# smartproj_ready.net
KiCad netlist of a schematic drawn in EAGLE
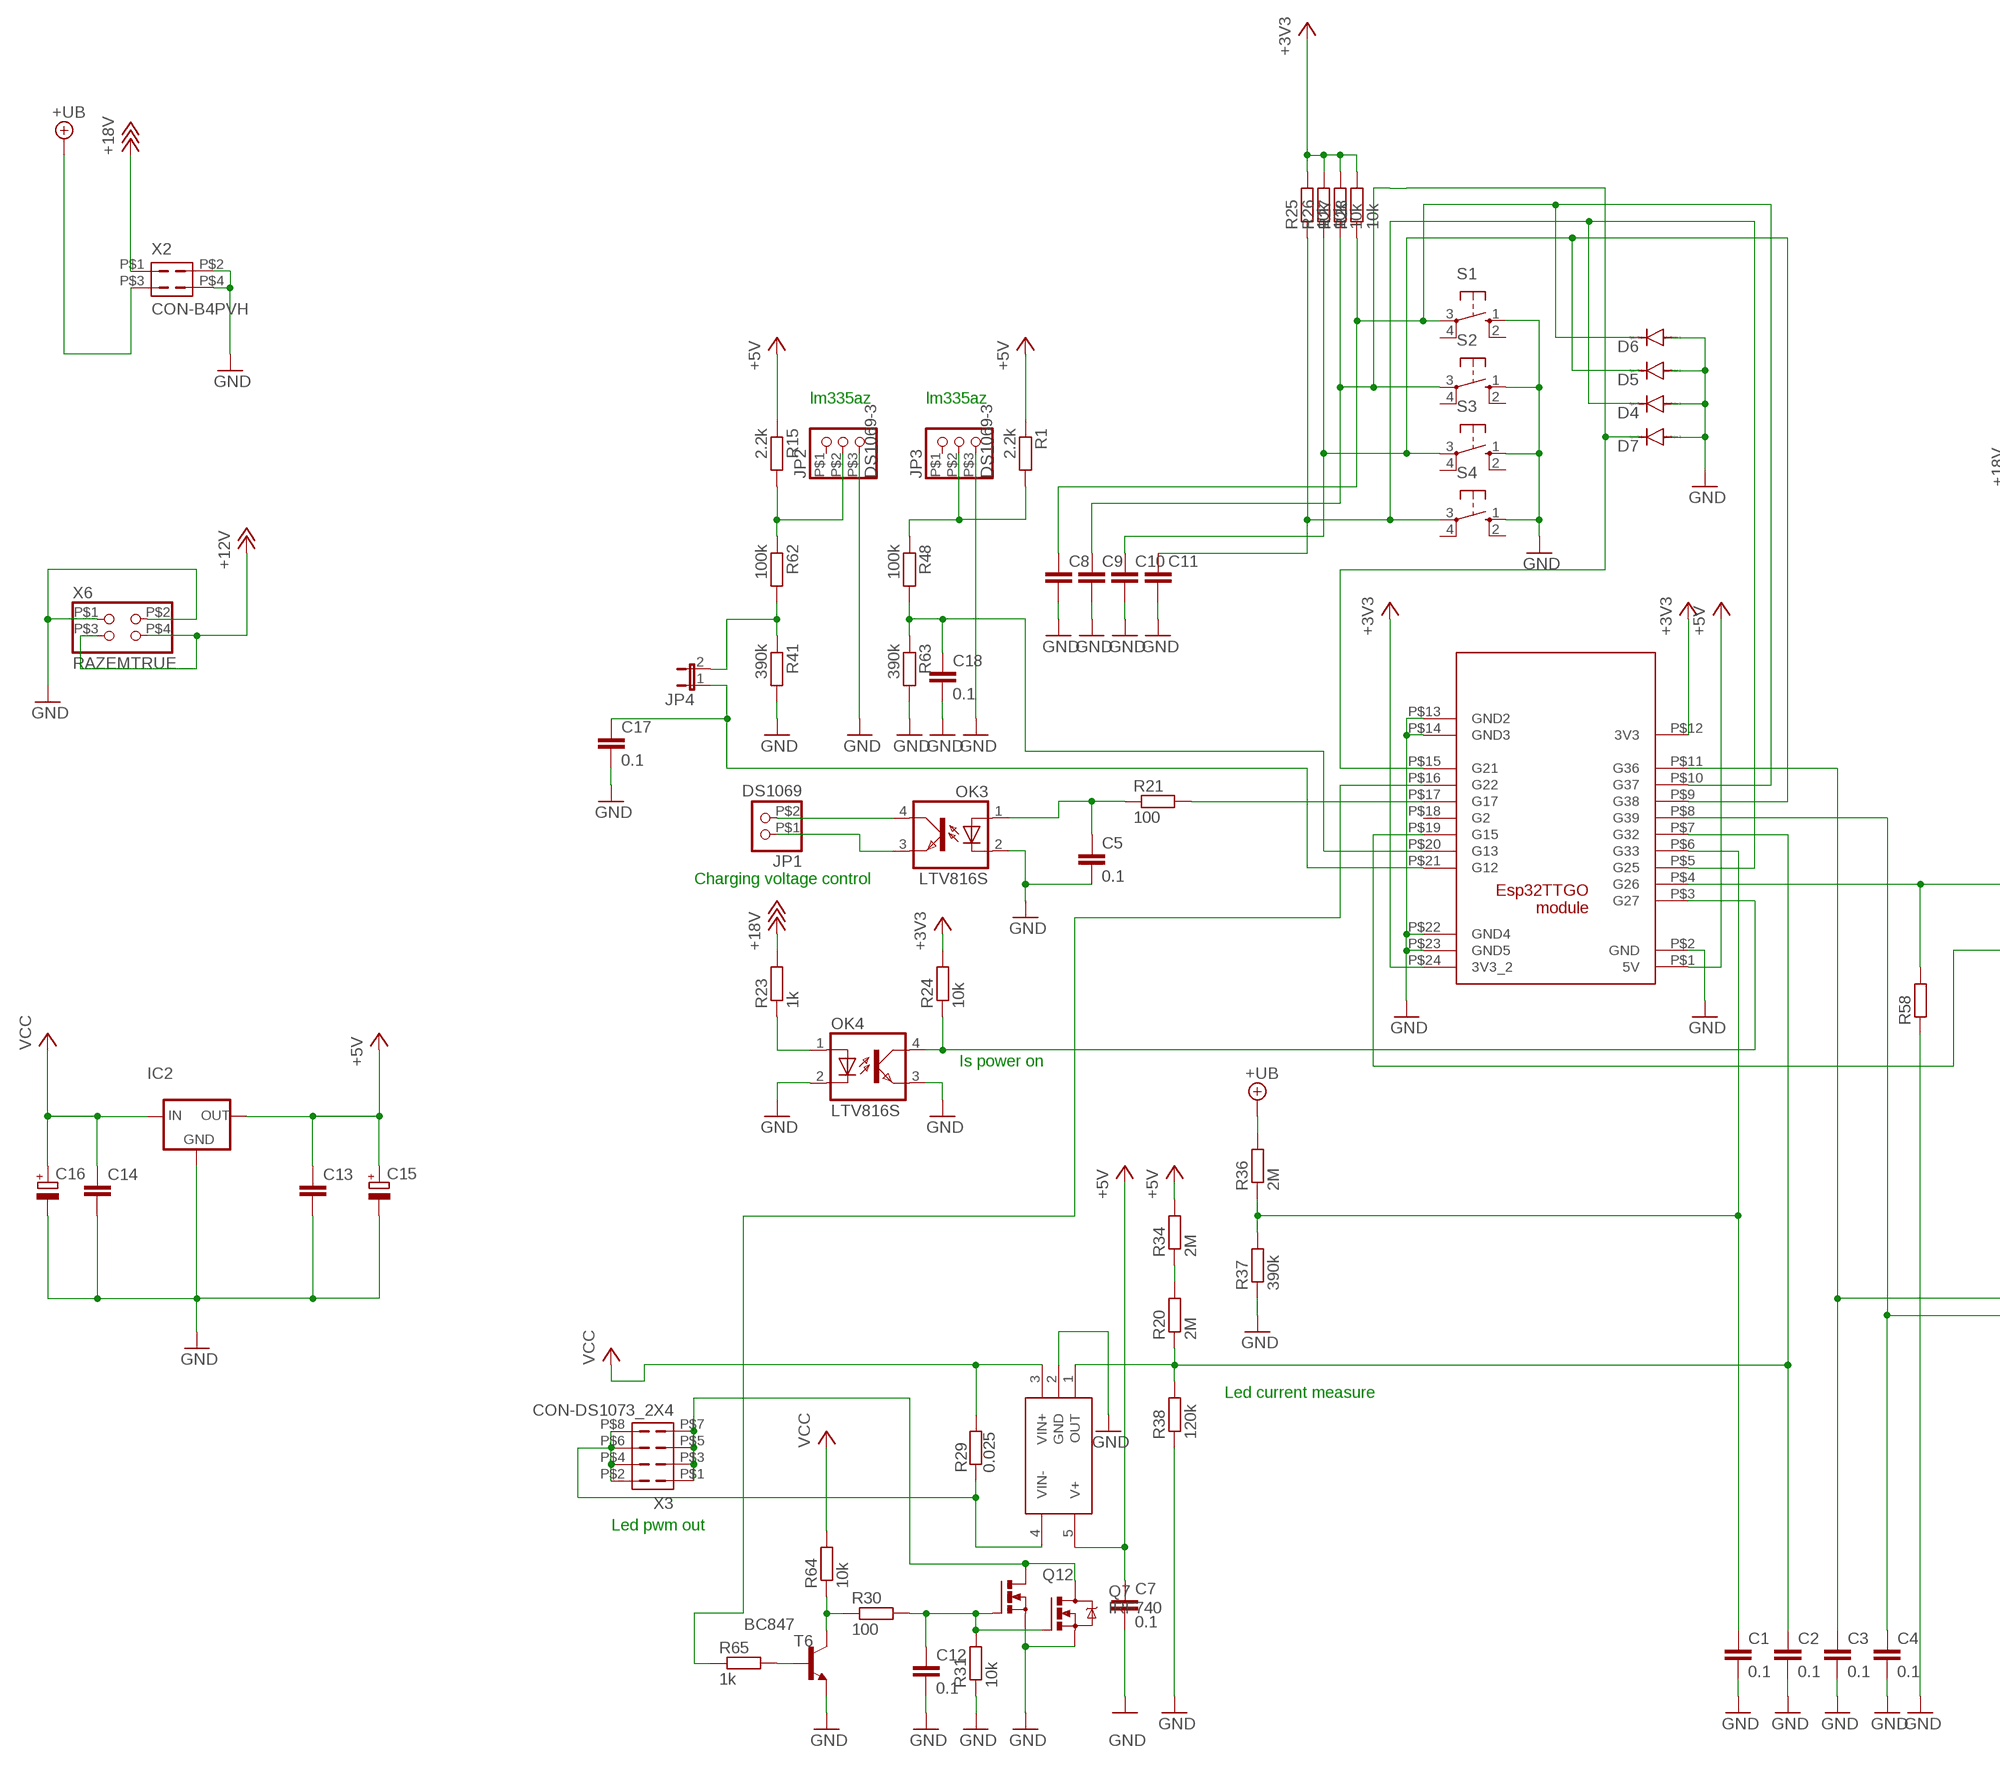
[diagram p0: schematic, sheet 1, part 1 of 2]
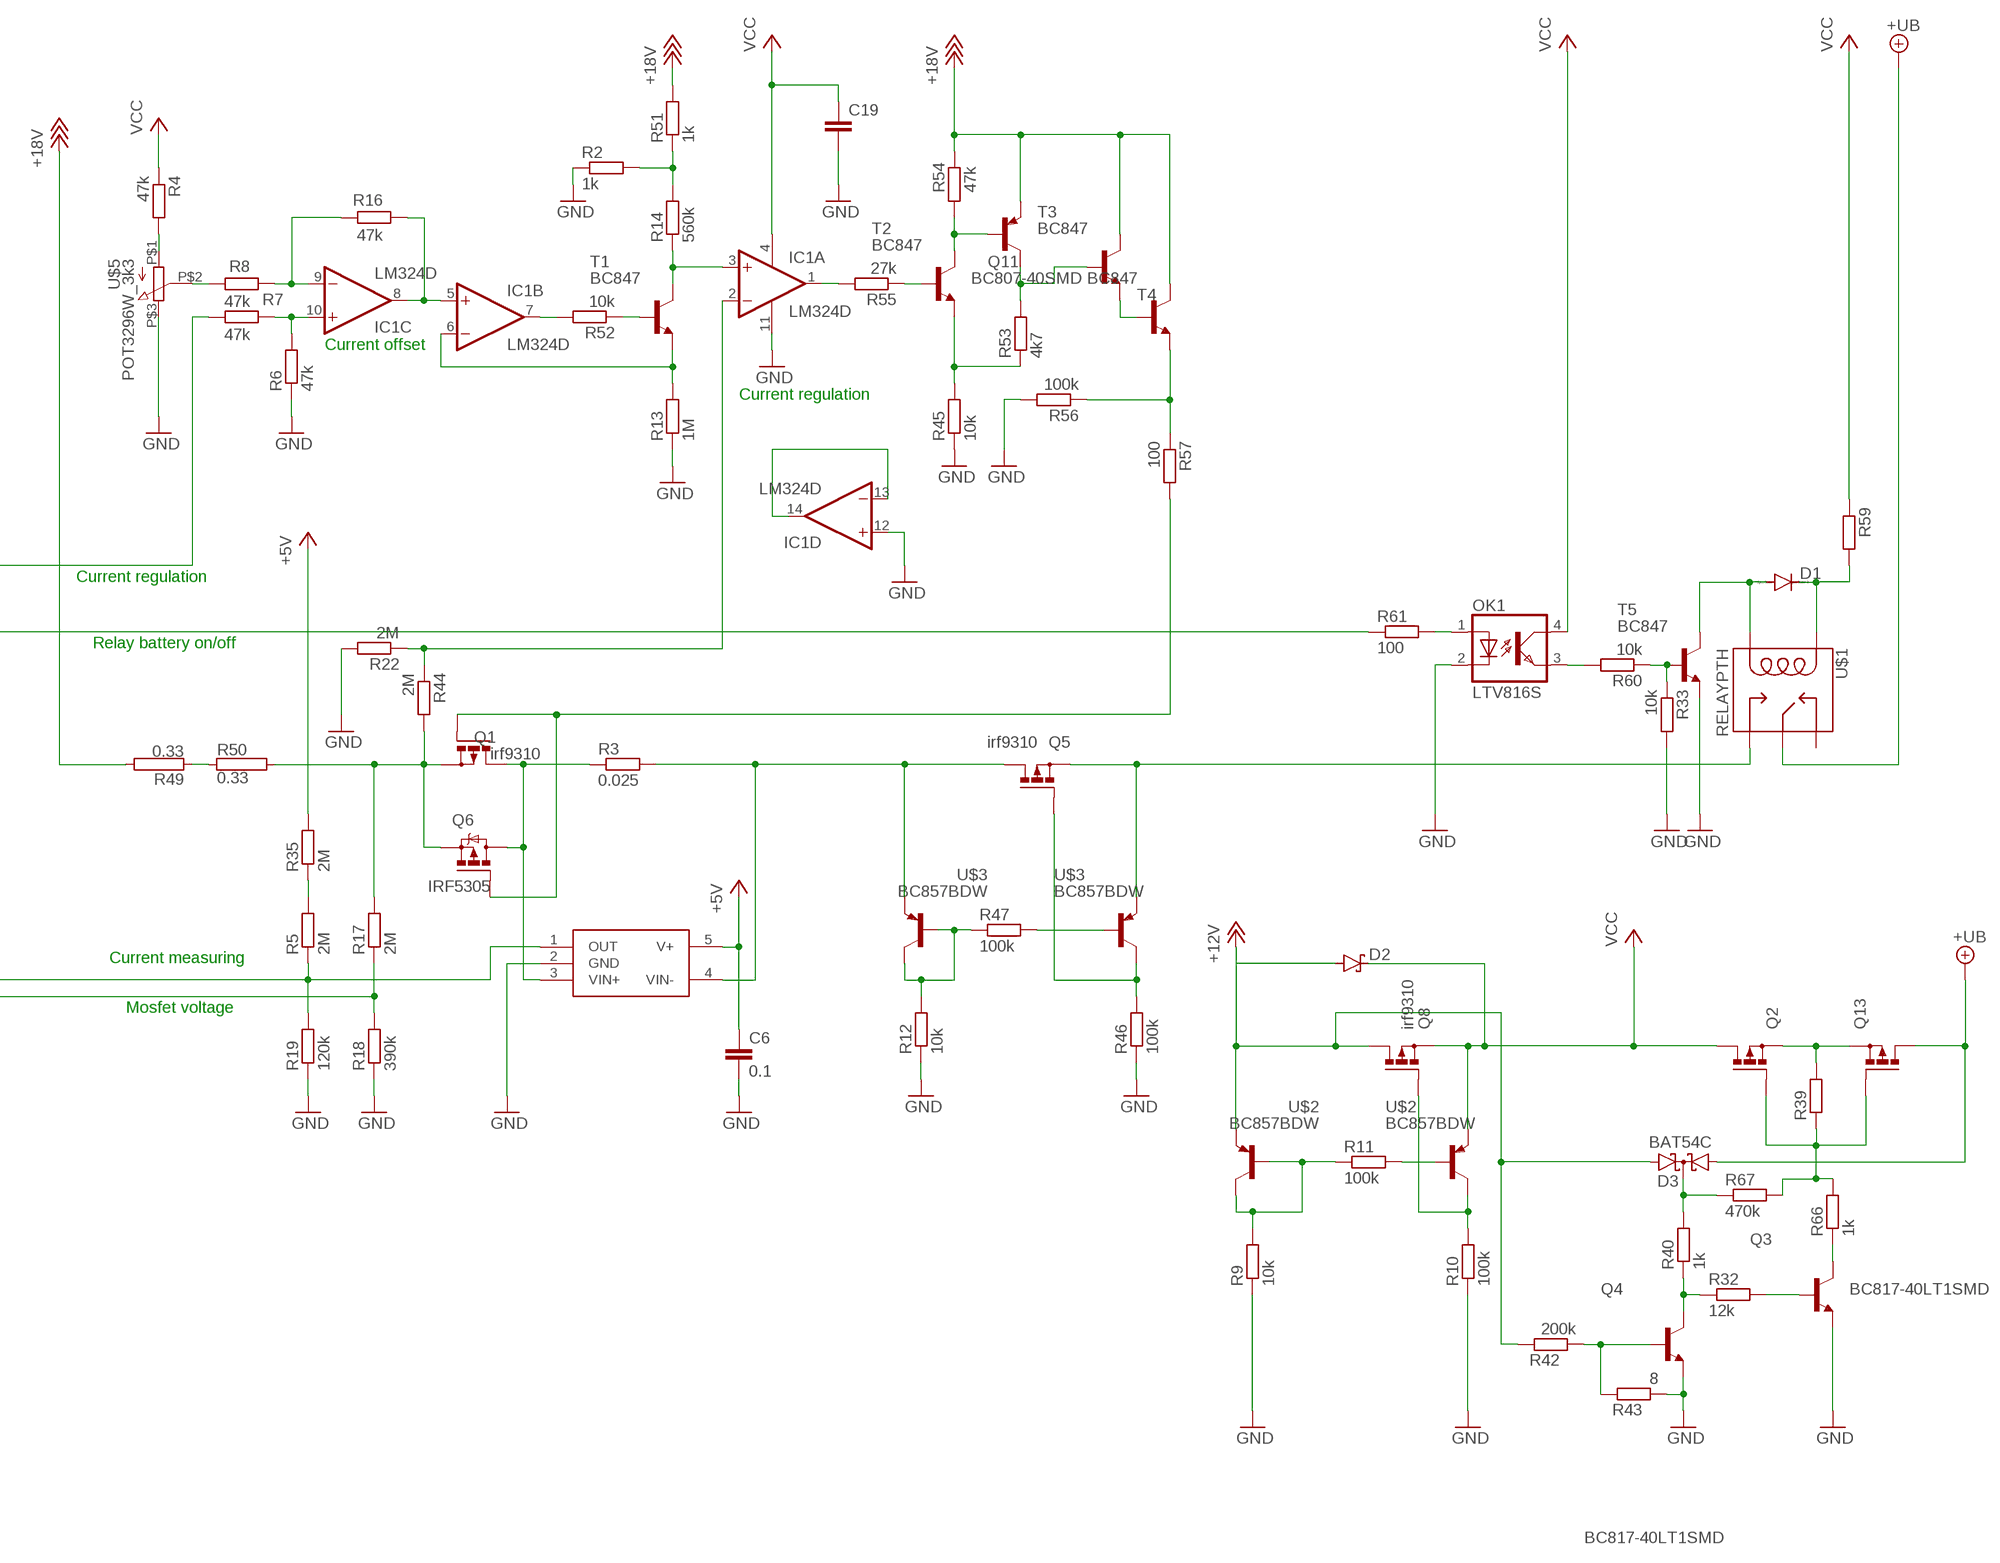
[diagram p1: schematic, sheet 1, part 2 of 2]

(export (version "E")
  (design (tool "Eeschema 10.0.6"))
  (components
    (comp (ref "C1")
      (value "0.1")
      (footprint "eagle-import:C0603K")
      (libsource (lib "eagle-import") (part "C-EUC0603K"))
    )
    (comp (ref "C2")
      (value "0.1")
      (footprint "eagle-import:C0603K")
      (libsource (lib "eagle-import") (part "C-EUC0603K"))
    )
    (comp (ref "C3")
      (value "0.1")
      (footprint "eagle-import:C0603K")
      (libsource (lib "eagle-import") (part "C-EUC0603K"))
    )
    (comp (ref "C4")
      (value "0.1")
      (footprint "eagle-import:C0603K")
      (libsource (lib "eagle-import") (part "C-EUC0603K"))
    )
    (comp (ref "C5")
      (value "0.1")
      (footprint "eagle-import:C0603K")
      (libsource (lib "eagle-import") (part "C-EUC0603K"))
    )
    (comp (ref "C6")
      (value "0.1")
      (footprint "eagle-import:C0603K")
      (libsource (lib "eagle-import") (part "C-EUC0603K"))
    )
    (comp (ref "C7")
      (value "0.1")
      (footprint "eagle-import:C0603K")
      (libsource (lib "eagle-import") (part "C-EUC0603K"))
    )
    (comp (ref "C8")
      (value "C-EUC0603K")
      (footprint "eagle-import:C0603K")
      (libsource (lib "eagle-import") (part "C-EUC0603K"))
    )
    (comp (ref "C9")
      (value "C-EUC0603K")
      (footprint "eagle-import:C0603K")
      (libsource (lib "eagle-import") (part "C-EUC0603K"))
    )
    (comp (ref "C10")
      (value "C-EUC0603K")
      (footprint "eagle-import:C0603K")
      (libsource (lib "eagle-import") (part "C-EUC0603K"))
    )
    (comp (ref "C11")
      (value "C-EUC0603K")
      (footprint "eagle-import:C0603K")
      (libsource (lib "eagle-import") (part "C-EUC0603K"))
    )
    (comp (ref "C12")
      (value "0.1")
      (footprint "eagle-import:C0603K")
      (libsource (lib "eagle-import") (part "C-EUC0603K"))
    )
    (comp (ref "C13")
      (value "C-EUC0603")
      (footprint "eagle-import:C0603")
      (libsource (lib "eagle-import") (part "C-EUC0603"))
    )
    (comp (ref "C14")
      (value "C-EUC0603")
      (footprint "eagle-import:C0603")
      (libsource (lib "eagle-import") (part "C-EUC0603"))
    )
    (comp (ref "C15")
      (value "CPOL-EUSMCE")
      (footprint "eagle-import:SMC_E")
      (libsource (lib "eagle-import") (part "CPOL-EUSMCE"))
    )
    (comp (ref "C16")
      (value "CPOL-EUSMCE")
      (footprint "eagle-import:SMC_E")
      (libsource (lib "eagle-import") (part "CPOL-EUSMCE"))
    )
    (comp (ref "C17")
      (value "0.1")
      (footprint "eagle-import:C0603K")
      (libsource (lib "eagle-import") (part "C-EUC0603K"))
    )
    (comp (ref "C18")
      (value "0.1")
      (footprint "eagle-import:C0603K")
      (libsource (lib "eagle-import") (part "C-EUC0603K"))
    )
    (comp (ref "C19")
      (value "C-EUC0603K")
      (footprint "eagle-import:C0603K")
      (libsource (lib "eagle-import") (part "C-EUC0603K"))
    )
    (comp (ref "D1")
      (value "DIODE-DO214AC")
      (footprint "eagle-import:DO214AC")
      (libsource (lib "eagle-import") (part "DIODE-DO214AC"))
    )
    (comp (ref "D2")
      (value "SCHOTTKY-DIODESMC")
      (footprint "eagle-import:SMC")
      (libsource (lib "eagle-import") (part "SCHOTTKY-DIODESMC"))
    )
    (comp (ref "D3")
      (value "BAT54C")
      (footprint "eagle-import:SOT23")
      (libsource (lib "eagle-import") (part "BAT54C"))
    )
    (comp (ref "D4")
      (value "DIODE-SOD323-W")
      (footprint "eagle-import:SOD323-W")
      (libsource (lib "eagle-import") (part "DIODE-SOD323-W"))
    )
    (comp (ref "D5")
      (value "DIODE-SOD323-W")
      (footprint "eagle-import:SOD323-W")
      (libsource (lib "eagle-import") (part "DIODE-SOD323-W"))
    )
    (comp (ref "D6")
      (value "DIODE-SOD323-W")
      (footprint "eagle-import:SOD323-W")
      (libsource (lib "eagle-import") (part "DIODE-SOD323-W"))
    )
    (comp (ref "D7")
      (value "DIODE-SOD323-W")
      (footprint "eagle-import:SOD323-W")
      (libsource (lib "eagle-import") (part "DIODE-SOD323-W"))
    )
    (comp (ref "IC1")
      (value "LM324D")
      (footprint "eagle-import:SO14")
      (libsource (lib "eagle-import") (part "LM324D"))
    )
    (comp (ref "IC2")
      (value "78XXS")
      (footprint "eagle-import:78XXS")
      (libsource (lib "eagle-import") (part "78XXS"))
    )
    (comp (ref "JP1")
      (value "DS1069")
      (footprint "eagle-import:DS1069-2")
      (libsource (lib "eagle-import") (part "DS1069"))
    )
    (comp (ref "JP2")
      (value "DS1069-3")
      (footprint "eagle-import:DS1069-3")
      (libsource (lib "eagle-import") (part "DS1069-3"))
    )
    (comp (ref "JP3")
      (value "DS1069-3")
      (footprint "eagle-import:DS1069-3")
      (libsource (lib "eagle-import") (part "DS1069-3"))
    )
    (comp (ref "JP4")
      (value "JP1E")
      (footprint "eagle-import:JP1")
      (libsource (lib "eagle-import") (part "JP1E"))
    )
    (comp (ref "OK1")
      (value "LTV816S")
      (footprint "eagle-import:DIL4-SMD")
      (libsource (lib "eagle-import") (part "LTV816S"))
    )
    (comp (ref "OK3")
      (value "LTV816S")
      (footprint "eagle-import:DIL4-SMD")
      (libsource (lib "eagle-import") (part "LTV816S"))
    )
    (comp (ref "OK4")
      (value "LTV816S")
      (footprint "eagle-import:DIL4-SMD")
      (libsource (lib "eagle-import") (part "LTV816S"))
    )
    (comp (ref "Q1")
      (value "irf9310")
      (footprint "eagle-import:SO-08")
      (libsource (lib "eagle-import") (part "P-MOSFET-SO8"))
    )
    (comp (ref "Q2")
      (value "P-MOSFET-SO8")
      (footprint "eagle-import:SO-08")
      (libsource (lib "eagle-import") (part "P-MOSFET-SO8"))
    )
    (comp (ref "Q3")
      (value "BC817-40LT1SMD")
      (footprint "eagle-import:SOT23-BEC")
      (libsource (lib "eagle-import") (part "BC817SMD-40LT1"))
    )
    (comp (ref "Q4")
      (value "BC817-40LT1SMD")
      (footprint "eagle-import:SOT23-BEC")
      (libsource (lib "eagle-import") (part "BC817SMD-40LT1"))
    )
    (comp (ref "Q5")
      (value "irf9310")
      (footprint "eagle-import:SO-08")
      (libsource (lib "eagle-import") (part "P-MOSFET-SO8"))
    )
    (comp (ref "Q6")
      (value "IRF5305")
      (footprint "eagle-import:TO220BV")
      (libsource (lib "eagle-import") (part "IRF9530"))
    )
    (comp (ref "Q7")
      (value "IRF740")
      (footprint "eagle-import:TO220BV")
      (libsource (lib "eagle-import") (part "IRF740"))
    )
    (comp (ref "Q8")
      (value "irf9310")
      (footprint "eagle-import:SO-08")
      (libsource (lib "eagle-import") (part "P-MOSFET-SO8"))
    )
    (comp (ref "Q11")
      (value "BC807-40SMD")
      (footprint "eagle-import:SOT23-BEC")
      (libsource (lib "eagle-import") (part "BC807SMD-40"))
    )
    (comp (ref "Q12")
      (value "N-MOSFET-SO8S")
      (footprint "eagle-import:SO-08")
      (libsource (lib "eagle-import") (part "N-MOSFET-SO8S"))
    )
    (comp (ref "Q13")
      (value "P-MOSFET-SO8")
      (footprint "eagle-import:SO-08")
      (libsource (lib "eagle-import") (part "P-MOSFET-SO8"))
    )
    (comp (ref "R1")
      (value "2.2k")
      (footprint "eagle-import:R0603")
      (libsource (lib "eagle-import") (part "resistor_348_R-EU_R0603"))
    )
    (comp (ref "R2")
      (value "1k")
      (footprint "eagle-import:R0603")
      (libsource (lib "eagle-import") (part "R-EU_R0603"))
    )
    (comp (ref "R3")
      (value "0.025")
      (footprint "eagle-import:R2512")
      (libsource (lib "eagle-import") (part "R-EU_R2512"))
    )
    (comp (ref "R4")
      (value "47k")
      (footprint "eagle-import:R0603")
      (libsource (lib "eagle-import") (part "resistor_348_R-EU_R0603"))
    )
    (comp (ref "R5")
      (value "2M")
      (footprint "eagle-import:R0603")
      (libsource (lib "eagle-import") (part "resistor_348_R-EU_R0603"))
    )
    (comp (ref "R6")
      (value "47k")
      (footprint "eagle-import:R0603")
      (libsource (lib "eagle-import") (part "resistor_348_R-EU_R0603"))
    )
    (comp (ref "R7")
      (value "47k")
      (footprint "eagle-import:R0603")
      (libsource (lib "eagle-import") (part "resistor_348_R-EU_R0603"))
    )
    (comp (ref "R8")
      (value "47k")
      (footprint "eagle-import:R0603")
      (libsource (lib "eagle-import") (part "resistor_348_R-EU_R0603"))
    )
    (comp (ref "R9")
      (value "10k")
      (footprint "eagle-import:R0603")
      (libsource (lib "eagle-import") (part "R-EU_R0603"))
    )
    (comp (ref "R10")
      (value "100k")
      (footprint "eagle-import:R0603")
      (libsource (lib "eagle-import") (part "R-EU_R0603"))
    )
    (comp (ref "R11")
      (value "100k")
      (footprint "eagle-import:R0603")
      (libsource (lib "eagle-import") (part "R-EU_R0603"))
    )
    (comp (ref "R12")
      (value "10k")
      (footprint "eagle-import:R0603")
      (libsource (lib "eagle-import") (part "R-EU_R0603"))
    )
    (comp (ref "R13")
      (value "1M")
      (footprint "eagle-import:R0603")
      (libsource (lib "eagle-import") (part "R-EU_R0603"))
    )
    (comp (ref "R14")
      (value "560k")
      (footprint "eagle-import:R0603")
      (libsource (lib "eagle-import") (part "R-EU_R0603"))
    )
    (comp (ref "R15")
      (value "2.2k")
      (footprint "eagle-import:R0603")
      (libsource (lib "eagle-import") (part "resistor_348_R-EU_R0603"))
    )
    (comp (ref "R16")
      (value "47k")
      (footprint "eagle-import:R0603")
      (libsource (lib "eagle-import") (part "resistor_348_R-EU_R0603"))
    )
    (comp (ref "R17")
      (value "2M")
      (footprint "eagle-import:R0603")
      (libsource (lib "eagle-import") (part "resistor_348_R-EU_R0603"))
    )
    (comp (ref "R18")
      (value "390k")
      (footprint "eagle-import:R0603")
      (libsource (lib "eagle-import") (part "resistor_348_R-EU_R0603"))
    )
    (comp (ref "R19")
      (value "120k")
      (footprint "eagle-import:R0603")
      (libsource (lib "eagle-import") (part "resistor_348_R-EU_R0603"))
    )
    (comp (ref "R20")
      (value "2M")
      (footprint "eagle-import:R0603")
      (libsource (lib "eagle-import") (part "resistor_348_R-EU_R0603"))
    )
    (comp (ref "R21")
      (value "100")
      (footprint "eagle-import:R0603")
      (libsource (lib "eagle-import") (part "resistor_348_R-EU_R0603"))
    )
    (comp (ref "R22")
      (value "2M")
      (footprint "eagle-import:R0603")
      (libsource (lib "eagle-import") (part "resistor_348_R-EU_R0603"))
    )
    (comp (ref "R23")
      (value "1k")
      (footprint "eagle-import:R0603")
      (libsource (lib "eagle-import") (part "R-EU_R0603"))
    )
    (comp (ref "R24")
      (value "10k")
      (footprint "eagle-import:R0603")
      (libsource (lib "eagle-import") (part "R-EU_R0603"))
    )
    (comp (ref "R25")
      (value "10k")
      (footprint "eagle-import:R0603")
      (libsource (lib "eagle-import") (part "R-EU_R0603"))
    )
    (comp (ref "R26")
      (value "10k")
      (footprint "eagle-import:R0603")
      (libsource (lib "eagle-import") (part "R-EU_R0603"))
    )
    (comp (ref "R27")
      (value "10k")
      (footprint "eagle-import:R0603")
      (libsource (lib "eagle-import") (part "R-EU_R0603"))
    )
    (comp (ref "R28")
      (value "10k")
      (footprint "eagle-import:R0603")
      (libsource (lib "eagle-import") (part "R-EU_R0603"))
    )
    (comp (ref "R29")
      (value "0.025")
      (footprint "eagle-import:R2512")
      (libsource (lib "eagle-import") (part "R-EU_R2512"))
    )
    (comp (ref "R30")
      (value "100")
      (footprint "eagle-import:R0603")
      (libsource (lib "eagle-import") (part "resistor_348_R-EU_R0603"))
    )
    (comp (ref "R31")
      (value "10k")
      (footprint "eagle-import:R0603")
      (libsource (lib "eagle-import") (part "resistor_348_R-EU_R0603"))
    )
    (comp (ref "R32")
      (value "12k")
      (footprint "eagle-import:R0603")
      (libsource (lib "eagle-import") (part "R-EU_R0603"))
    )
    (comp (ref "R33")
      (value "10k")
      (footprint "eagle-import:R0603")
      (libsource (lib "eagle-import") (part "R-EU_R0603"))
    )
    (comp (ref "R34")
      (value "2M")
      (footprint "eagle-import:R0603")
      (libsource (lib "eagle-import") (part "resistor_348_R-EU_R0603"))
    )
    (comp (ref "R35")
      (value "2M")
      (footprint "eagle-import:R0603")
      (libsource (lib "eagle-import") (part "resistor_348_R-EU_R0603"))
    )
    (comp (ref "R36")
      (value "2M")
      (footprint "eagle-import:R0603")
      (libsource (lib "eagle-import") (part "R-EU_R0603"))
    )
    (comp (ref "R37")
      (value "390k")
      (footprint "eagle-import:R0603")
      (libsource (lib "eagle-import") (part "R-EU_R0603"))
    )
    (comp (ref "R38")
      (value "120k")
      (footprint "eagle-import:R0603")
      (libsource (lib "eagle-import") (part "resistor_348_R-EU_R0603"))
    )
    (comp (ref "R39")
      (value "R-EU_R0603")
      (footprint "eagle-import:R0603")
      (libsource (lib "eagle-import") (part "R-EU_R0603"))
    )
    (comp (ref "R40")
      (value "1k")
      (footprint "eagle-import:R0603")
      (libsource (lib "eagle-import") (part "R-EU_R0603"))
    )
    (comp (ref "R41")
      (value "390k")
      (footprint "eagle-import:R0603")
      (libsource (lib "eagle-import") (part "resistor_348_R-EU_R0603"))
    )
    (comp (ref "R42")
      (value "200k")
      (footprint "eagle-import:R0603")
      (libsource (lib "eagle-import") (part "R-EU_R0603"))
    )
    (comp (ref "R43")
      (value "8")
      (footprint "eagle-import:R0603")
      (libsource (lib "eagle-import") (part "R-EU_R0603"))
    )
    (comp (ref "R44")
      (value "2M")
      (footprint "eagle-import:R0603")
      (libsource (lib "eagle-import") (part "resistor_348_R-EU_R0603"))
    )
    (comp (ref "R45")
      (value "10k")
      (footprint "eagle-import:R0603")
      (libsource (lib "eagle-import") (part "R-EU_R0603"))
    )
    (comp (ref "R46")
      (value "100k")
      (footprint "eagle-import:R0603")
      (libsource (lib "eagle-import") (part "R-EU_R0603"))
    )
    (comp (ref "R47")
      (value "100k")
      (footprint "eagle-import:R0603")
      (libsource (lib "eagle-import") (part "R-EU_R0603"))
    )
    (comp (ref "R48")
      (value "100k")
      (footprint "eagle-import:R0603")
      (libsource (lib "eagle-import") (part "resistor_348_R-EU_R0603"))
    )
    (comp (ref "R49")
      (value "0.33")
      (footprint "eagle-import:CA4220")
      (libsource (lib "eagle-import") (part "RCA4220"))
    )
    (comp (ref "R50")
      (value "0.33")
      (footprint "eagle-import:CA4220")
      (libsource (lib "eagle-import") (part "RCA4220"))
    )
    (comp (ref "R51")
      (value "1k")
      (footprint "eagle-import:R0603")
      (libsource (lib "eagle-import") (part "R-EU_R0603"))
    )
    (comp (ref "R52")
      (value "10k")
      (footprint "eagle-import:R0603")
      (libsource (lib "eagle-import") (part "R-EU_R0603"))
    )
    (comp (ref "R53")
      (value "4k7")
      (footprint "eagle-import:R0603")
      (libsource (lib "eagle-import") (part "R-EU_R0603"))
    )
    (comp (ref "R54")
      (value "47k")
      (footprint "eagle-import:R0603")
      (libsource (lib "eagle-import") (part "R-EU_R0603"))
    )
    (comp (ref "R55")
      (value "27k")
      (footprint "eagle-import:R0603")
      (libsource (lib "eagle-import") (part "R-EU_R0603"))
    )
    (comp (ref "R56")
      (value "100k")
      (footprint "eagle-import:R0603")
      (libsource (lib "eagle-import") (part "R-EU_R0603"))
    )
    (comp (ref "R57")
      (value "100")
      (footprint "eagle-import:R0603")
      (libsource (lib "eagle-import") (part "R-EU_R0603"))
    )
    (comp (ref "R58")
      (value "R-EU_R0603")
      (footprint "eagle-import:R0603")
      (libsource (lib "eagle-import") (part "R-EU_R0603"))
    )
    (comp (ref "R59")
      (value "R-EU_R1206")
      (footprint "eagle-import:R1206")
      (libsource (lib "eagle-import") (part "R-EU_R1206"))
    )
    (comp (ref "R60")
      (value "10k")
      (footprint "eagle-import:R0603")
      (libsource (lib "eagle-import") (part "R-EU_R0603"))
    )
    (comp (ref "R61")
      (value "100")
      (footprint "eagle-import:R0603")
      (libsource (lib "eagle-import") (part "R-EU_R0603"))
    )
    (comp (ref "R62")
      (value "100k")
      (footprint "eagle-import:R0603")
      (libsource (lib "eagle-import") (part "resistor_348_R-EU_R0603"))
    )
    (comp (ref "R63")
      (value "390k")
      (footprint "eagle-import:R0603")
      (libsource (lib "eagle-import") (part "resistor_348_R-EU_R0603"))
    )
    (comp (ref "R64")
      (value "10k")
      (footprint "eagle-import:R0603")
      (libsource (lib "eagle-import") (part "resistor_348_R-EU_R0603"))
    )
    (comp (ref "R65")
      (value "1k")
      (footprint "eagle-import:R0603")
      (libsource (lib "eagle-import") (part "resistor_348_R-EU_R0603"))
    )
    (comp (ref "R66")
      (value "1k")
      (footprint "eagle-import:R0603")
      (libsource (lib "eagle-import") (part "R-EU_R0603"))
    )
    (comp (ref "R67")
      (value "470k")
      (footprint "eagle-import:R0603")
      (libsource (lib "eagle-import") (part "R-EU_R0603"))
    )
    (comp (ref "S1")
      (value "10-XX")
      (footprint "eagle-import:B3F-10XX")
      (fields (field (name "MPN") "B3F-1000"))
      (libsource (lib "eagle-import") (part "10-XX"))
    )
    (comp (ref "S2")
      (value "10-XX")
      (footprint "eagle-import:B3F-10XX")
      (fields (field (name "MPN") "B3F-1000"))
      (libsource (lib "eagle-import") (part "10-XX"))
    )
    (comp (ref "S3")
      (value "10-XX")
      (footprint "eagle-import:B3F-10XX")
      (fields (field (name "MPN") "B3F-1000"))
      (libsource (lib "eagle-import") (part "10-XX"))
    )
    (comp (ref "S4")
      (value "10-XX")
      (footprint "eagle-import:B3F-10XX")
      (fields (field (name "MPN") "B3F-1000"))
      (libsource (lib "eagle-import") (part "10-XX"))
    )
    (comp (ref "T1")
      (value "BC847")
      (footprint "eagle-import:SOT23")
      (libsource (lib "eagle-import") (part "BC847"))
    )
    (comp (ref "T2")
      (value "BC847")
      (footprint "eagle-import:SOT23")
      (libsource (lib "eagle-import") (part "BC847"))
    )
    (comp (ref "T3")
      (value "BC847")
      (footprint "eagle-import:SOT23")
      (libsource (lib "eagle-import") (part "BC847"))
    )
    (comp (ref "T4")
      (value "BC847")
      (footprint "eagle-import:SOT23")
      (libsource (lib "eagle-import") (part "BC847"))
    )
    (comp (ref "T5")
      (value "BC847")
      (footprint "eagle-import:SOT23")
      (libsource (lib "eagle-import") (part "BC847"))
    )
    (comp (ref "T6")
      (value "BC847")
      (footprint "eagle-import:SOT23")
      (libsource (lib "eagle-import") (part "BC847"))
    )
    (comp (ref "U$1")
      (value "RELAYPTH")
      (footprint "eagle-import:SRD-05VDC-SL-C")
      (libsource (lib "eagle-import") (part "RELAYPTH"))
    )
    (comp (ref "U$2")
      (value "BC857BDW")
      (footprint "eagle-import:SOT363-INFINION")
      (libsource (lib "eagle-import") (part "BC857BDW"))
    )
    (comp (ref "U$3")
      (value "BC857BDW")
      (footprint "eagle-import:SOT363-INFINION")
      (libsource (lib "eagle-import") (part "BC857BDW"))
    )
    (comp (ref "U$5")
      (value "POT3296W_3k3")
      (footprint "eagle-import:3296W")
      (libsource (lib "eagle-import") (part "POT3296W"))
    )
    (comp (ref "U1")
      (value "ESP32TTGO")
      (footprint "eagle-import:ESP32TTGODIP")
      (libsource (lib "eagle-import") (part "ESP32TTGO"))
    )
    (comp (ref "U3")
      (value "INA138")
      (footprint "eagle-import:SOT23-DBV")
      (libsource (lib "eagle-import") (part "INA138"))
    )
    (comp (ref "U4")
      (value "INA138")
      (footprint "eagle-import:SOT23-DBV")
      (libsource (lib "eagle-import") (part "INA138"))
    )
    (comp (ref "X2")
      (value "CON-B4PVH")
      (footprint "eagle-import:B4PVH4")
      (libsource (lib "eagle-import") (part "CON-B4PVH"))
    )
    (comp (ref "X3")
      (value "CON-DS1073_2X4")
      (footprint "eagle-import:DS1073_2X4")
      (libsource (lib "eagle-import") (part "CON-DS1073_2X4"))
    )
    (comp (ref "X6")
      (value "RAZEMTRUE")
      (footprint "eagle-import:DS1073_2X2N2")
      (libsource (lib "eagle-import") (part "RAZEMTRUE"))
    )
  )
  (nets
    (net (code "1") (name "+3V3") (class "Default")
      (node (ref "R24") (pin "2") (pinfunction "2_2") (pintype "passive"))
      (node (ref "R25") (pin "2") (pinfunction "2_2") (pintype "passive"))
      (node (ref "R26") (pin "2") (pinfunction "2_2") (pintype "passive"))
      (node (ref "R27") (pin "2") (pinfunction "2_2") (pintype "passive"))
      (node (ref "R28") (pin "2") (pinfunction "2_2") (pintype "passive"))
      (node (ref "U1") (pin "P$12") (pinfunction "3V3_P$12") (pintype "power_in"))
      (node (ref "U1") (pin "P$24") (pinfunction "3V3_2_P$24") (pintype "power_in"))
    )
    (net (code "2") (name "+5V") (class "Default")
      (node (ref "C13") (pin "1") (pinfunction "1_1") (pintype "passive"))
      (node (ref "C15") (pin "+") (pinfunction "+_+") (pintype "passive"))
      (node (ref "C6") (pin "1") (pinfunction "1_1") (pintype "passive"))
      (node (ref "C7") (pin "1") (pinfunction "1_1") (pintype "passive"))
      (node (ref "IC2") (pin "OUT") (pinfunction "OUT_OUT") (pintype "passive"))
      (node (ref "R1") (pin "1") (pinfunction "1_1") (pintype "passive"))
      (node (ref "R15") (pin "1") (pinfunction "1_1") (pintype "passive"))
      (node (ref "R34") (pin "2") (pinfunction "2_2") (pintype "passive"))
      (node (ref "R35") (pin "2") (pinfunction "2_2") (pintype "passive"))
      (node (ref "U1") (pin "P$1") (pinfunction "5V_P$1") (pintype "power_in"))
      (node (ref "U3") (pin "5") (pinfunction "V+_5") (pintype "input"))
      (node (ref "U4") (pin "5") (pinfunction "V+_5") (pintype "input"))
    )
    (net (code "3") (name "+12V") (class "Default")
      (node (ref "D2") (pin "A") (pinfunction "A_A") (pintype "passive"))
      (node (ref "D3") (pin "2") (pinfunction "A2_2") (pintype "passive"))
      (node (ref "Q8") (pin "5") (pinfunction "D_5") (pintype "passive"))
      (node (ref "Q8") (pin "6") (pinfunction "D_6") (pintype "passive"))
      (node (ref "Q8") (pin "7") (pinfunction "D_7") (pintype "passive"))
      (node (ref "Q8") (pin "8") (pinfunction "D_8") (pintype "passive"))
      (node (ref "R42") (pin "2") (pinfunction "2_2") (pintype "passive"))
      (node (ref "U$2") (pin "1") (pinfunction "E1_1") (pintype "passive"))
      (node (ref "X6") (pin "P$3") (pinfunction "3_P$3") (pintype "passive"))
      (node (ref "X6") (pin "P$4") (pinfunction "4_P$4") (pintype "passive"))
    )
    (net (code "4") (name "+18V") (class "Default")
      (node (ref "Q11") (pin "E") (pinfunction "E_E") (pintype "passive"))
      (node (ref "R23") (pin "2") (pinfunction "2_2") (pintype "passive"))
      (node (ref "R49") (pin "2") (pinfunction "2_2") (pintype "passive"))
      (node (ref "R51") (pin "2") (pinfunction "2_2") (pintype "passive"))
      (node (ref "R54") (pin "2") (pinfunction "2_2") (pintype "passive"))
      (node (ref "T3") (pin "3") (pinfunction "C_3") (pintype "passive"))
      (node (ref "T4") (pin "3") (pinfunction "C_3") (pintype "passive"))
      (node (ref "X2") (pin "P$1") (pinfunction "1_P$1") (pintype "passive"))
    )
    (net (code "5") (name "+UB") (class "Default")
      (node (ref "D3") (pin "1") (pinfunction "A1_1") (pintype "passive"))
      (node (ref "Q13") (pin "5") (pinfunction "D_5") (pintype "passive"))
      (node (ref "Q13") (pin "6") (pinfunction "D_6") (pintype "passive"))
      (node (ref "Q13") (pin "7") (pinfunction "D_7") (pintype "passive"))
      (node (ref "Q13") (pin "8") (pinfunction "D_8") (pintype "passive"))
      (node (ref "R36") (pin "2") (pinfunction "2_2") (pintype "passive"))
      (node (ref "U$1") (pin "SWCOMMON") (pinfunction "SWCOMMON_SWCOMMON") (pintype "bidirectional"))
      (node (ref "X2") (pin "P$3") (pinfunction "3_P$3") (pintype "passive"))
    )
    (net (code "6") (name "GND") (class "Default")
      (node (ref "C1") (pin "2") (pinfunction "2_2") (pintype "passive"))
      (node (ref "C10") (pin "2") (pinfunction "2_2") (pintype "passive"))
      (node (ref "C11") (pin "2") (pinfunction "2_2") (pintype "passive"))
      (node (ref "C12") (pin "2") (pinfunction "2_2") (pintype "passive"))
      (node (ref "C13") (pin "2") (pinfunction "2_2") (pintype "passive"))
      (node (ref "C14") (pin "2") (pinfunction "2_2") (pintype "passive"))
      (node (ref "C15") (pin "-") (pinfunction "-_-") (pintype "passive"))
      (node (ref "C16") (pin "-") (pinfunction "-_-") (pintype "passive"))
      (node (ref "C17") (pin "2") (pinfunction "2_2") (pintype "passive"))
      (node (ref "C18") (pin "2") (pinfunction "2_2") (pintype "passive"))
      (node (ref "C19") (pin "2") (pinfunction "2_2") (pintype "passive"))
      (node (ref "C2") (pin "2") (pinfunction "2_2") (pintype "passive"))
      (node (ref "C3") (pin "2") (pinfunction "2_2") (pintype "passive"))
      (node (ref "C4") (pin "2") (pinfunction "2_2") (pintype "passive"))
      (node (ref "C5") (pin "2") (pinfunction "2_2") (pintype "passive"))
      (node (ref "C6") (pin "2") (pinfunction "2_2") (pintype "passive"))
      (node (ref "C7") (pin "2") (pinfunction "2_2") (pintype "passive"))
      (node (ref "C8") (pin "2") (pinfunction "2_2") (pintype "passive"))
      (node (ref "C9") (pin "2") (pinfunction "2_2") (pintype "passive"))
      (node (ref "D4") (pin "A") (pinfunction "A_A") (pintype "passive"))
      (node (ref "D5") (pin "A") (pinfunction "A_A") (pintype "passive"))
      (node (ref "D6") (pin "A") (pinfunction "A_A") (pintype "passive"))
      (node (ref "D7") (pin "A") (pinfunction "A_A") (pintype "passive"))
      (node (ref "IC1") (pin "11") (pinfunction "V-_11") (pintype "power_in"))
      (node (ref "IC1") (pin "12") (pinfunction "+IN_12") (pintype "input"))
      (node (ref "IC2") (pin "GND") (pinfunction "GND_GND") (pintype "input"))
      (node (ref "JP2") (pin "P$3") (pinfunction "3_P$3") (pintype "passive"))
      (node (ref "JP3") (pin "P$3") (pinfunction "3_P$3") (pintype "passive"))
      (node (ref "OK1") (pin "2") (pinfunction "C_2") (pintype "passive"))
      (node (ref "OK3") (pin "2") (pinfunction "C_2") (pintype "passive"))
      (node (ref "OK4") (pin "2") (pinfunction "C_2") (pintype "passive"))
      (node (ref "OK4") (pin "3") (pinfunction "EMIT_3") (pintype "passive"))
      (node (ref "Q12") (pin "1") (pinfunction "S_1") (pintype "passive"))
      (node (ref "Q12") (pin "2") (pinfunction "S_2") (pintype "passive"))
      (node (ref "Q12") (pin "3") (pinfunction "S_3") (pintype "passive"))
      (node (ref "Q3") (pin "E") (pinfunction "E_E") (pintype "passive"))
      (node (ref "Q4") (pin "E") (pinfunction "E_E") (pintype "passive"))
      (node (ref "Q7") (pin "S") (pinfunction "S_S") (pintype "passive"))
      (node (ref "R10") (pin "1") (pinfunction "1_1") (pintype "passive"))
      (node (ref "R12") (pin "1") (pinfunction "1_1") (pintype "passive"))
      (node (ref "R13") (pin "1") (pinfunction "1_1") (pintype "passive"))
      (node (ref "R18") (pin "1") (pinfunction "1_1") (pintype "passive"))
      (node (ref "R19") (pin "1") (pinfunction "1_1") (pintype "passive"))
      (node (ref "R2") (pin "1") (pinfunction "1_1") (pintype "passive"))
      (node (ref "R22") (pin "2") (pinfunction "2_2") (pintype "passive"))
      (node (ref "R31") (pin "1") (pinfunction "1_1") (pintype "passive"))
      (node (ref "R33") (pin "2") (pinfunction "2_2") (pintype "passive"))
      (node (ref "R37") (pin "1") (pinfunction "1_1") (pintype "passive"))
      (node (ref "R38") (pin "1") (pinfunction "1_1") (pintype "passive"))
      (node (ref "R41") (pin "2") (pinfunction "2_2") (pintype "passive"))
      (node (ref "R43") (pin "1") (pinfunction "1_1") (pintype "passive"))
      (node (ref "R45") (pin "1") (pinfunction "1_1") (pintype "passive"))
      (node (ref "R46") (pin "1") (pinfunction "1_1") (pintype "passive"))
      (node (ref "R56") (pin "2") (pinfunction "2_2") (pintype "passive"))
      (node (ref "R58") (pin "1") (pinfunction "1_1") (pintype "passive"))
      (node (ref "R6") (pin "1") (pinfunction "1_1") (pintype "passive"))
      (node (ref "R63") (pin "2") (pinfunction "2_2") (pintype "passive"))
      (node (ref "R9") (pin "1") (pinfunction "1_1") (pintype "passive"))
      (node (ref "S1") (pin "1") (pinfunction "S_1") (pintype "passive"))
      (node (ref "S2") (pin "1") (pinfunction "S_1") (pintype "passive"))
      (node (ref "S3") (pin "1") (pinfunction "S_1") (pintype "passive"))
      (node (ref "S4") (pin "1") (pinfunction "S_1") (pintype "passive"))
      (node (ref "T5") (pin "2") (pinfunction "E_2") (pintype "passive"))
      (node (ref "T6") (pin "2") (pinfunction "E_2") (pintype "passive"))
      (node (ref "U$5") (pin "P$3") (pinfunction "E_P$3") (pintype "passive"))
      (node (ref "U1") (pin "P$13") (pinfunction "GND2_P$13") (pintype "power_in"))
      (node (ref "U1") (pin "P$14") (pinfunction "GND3_P$14") (pintype "power_in"))
      (node (ref "U1") (pin "P$2") (pinfunction "GND_P$2") (pintype "power_in"))
      (node (ref "U1") (pin "P$22") (pinfunction "GND4_P$22") (pintype "power_in"))
      (node (ref "U1") (pin "P$23") (pinfunction "GND5_P$23") (pintype "power_in"))
      (node (ref "U3") (pin "2") (pinfunction "GND_2") (pintype "power_in"))
      (node (ref "U4") (pin "2") (pinfunction "GND_2") (pintype "power_in"))
      (node (ref "X2") (pin "P$2") (pinfunction "2_P$2") (pintype "passive"))
      (node (ref "X2") (pin "P$4") (pinfunction "4_P$4") (pintype "passive"))
      (node (ref "X6") (pin "P$1") (pinfunction "1_P$1") (pintype "passive"))
      (node (ref "X6") (pin "P$2") (pinfunction "2_P$2") (pintype "passive"))
    )
    (net (code "7") (name "Net-(D1-PadC)") (class "Default")
      (node (ref "D1") (pin "C") (pinfunction "C_C") (pintype "passive"))
      (node (ref "R59") (pin "2") (pinfunction "2_2") (pintype "passive"))
      (node (ref "U$1") (pin "COIL1") (pinfunction "COIL1_COIL1") (pintype "bidirectional"))
    )
    (net (code "8") (name "Net-(D3-CC)") (class "Default")
      (node (ref "D3") (pin "3") (pinfunction "CC_3") (pintype "passive"))
      (node (ref "R40") (pin "2") (pinfunction "2_2") (pintype "passive"))
      (node (ref "R67") (pin "1") (pinfunction "1_1") (pintype "passive"))
    )
    (net (code "9") (name "Net-(IC1A-+IN)") (class "Default")
      (node (ref "IC1") (pin "3") (pinfunction "+IN_3") (pintype "input"))
      (node (ref "R14") (pin "1") (pinfunction "1_1") (pintype "passive"))
      (node (ref "T1") (pin "3") (pinfunction "C_3") (pintype "passive"))
    )
    (net (code "10") (name "Net-(IC1A--IN)") (class "Default")
      (node (ref "IC1") (pin "2") (pinfunction "-IN_2") (pintype "input"))
      (node (ref "R22") (pin "1") (pinfunction "1_1") (pintype "passive"))
      (node (ref "R44") (pin "1") (pinfunction "1_1") (pintype "passive"))
    )
    (net (code "11") (name "Net-(IC1A-OUT)") (class "Default")
      (node (ref "IC1") (pin "1") (pinfunction "OUT_1") (pintype "output"))
      (node (ref "R55") (pin "2") (pinfunction "2_2") (pintype "passive"))
    )
    (net (code "12") (name "Net-(IC1B-+IN)") (class "Default")
      (node (ref "IC1") (pin "5") (pinfunction "+IN_5") (pintype "input"))
      (node (ref "IC1") (pin "8") (pinfunction "OUT_8") (pintype "output"))
      (node (ref "R16") (pin "1") (pinfunction "1_1") (pintype "passive"))
    )
    (net (code "13") (name "Net-(IC1B--IN)") (class "Default")
      (node (ref "IC1") (pin "6") (pinfunction "-IN_6") (pintype "input"))
      (node (ref "R13") (pin "2") (pinfunction "2_2") (pintype "passive"))
      (node (ref "T1") (pin "2") (pinfunction "E_2") (pintype "passive"))
    )
    (net (code "14") (name "Net-(IC1B-OUT)") (class "Default")
      (node (ref "IC1") (pin "7") (pinfunction "OUT_7") (pintype "output"))
      (node (ref "R52") (pin "2") (pinfunction "2_2") (pintype "passive"))
    )
    (net (code "15") (name "Net-(IC1C-+IN)") (class "Default")
      (node (ref "IC1") (pin "10") (pinfunction "+IN_10") (pintype "input"))
      (node (ref "R6") (pin "2") (pinfunction "2_2") (pintype "passive"))
      (node (ref "R7") (pin "1") (pinfunction "1_1") (pintype "passive"))
    )
    (net (code "16") (name "Net-(IC1C--IN)") (class "Default")
      (node (ref "IC1") (pin "9") (pinfunction "-IN_9") (pintype "input"))
      (node (ref "R16") (pin "2") (pinfunction "2_2") (pintype "passive"))
      (node (ref "R8") (pin "1") (pinfunction "1_1") (pintype "passive"))
    )
    (net (code "17") (name "Net-(IC1D--IN)") (class "Default")
      (node (ref "IC1") (pin "13") (pinfunction "-IN_13") (pintype "input"))
      (node (ref "IC1") (pin "14") (pinfunction "OUT_14") (pintype "output"))
    )
    (net (code "18") (name "Net-(JP1-1)") (class "Default")
      (node (ref "JP1") (pin "P$1") (pinfunction "1_P$1") (pintype "passive"))
      (node (ref "OK3") (pin "3") (pinfunction "EMIT_3") (pintype "passive"))
    )
    (net (code "19") (name "Net-(JP1-2)") (class "Default")
      (node (ref "JP1") (pin "P$2") (pinfunction "2_P$2") (pintype "passive"))
      (node (ref "OK3") (pin "4") (pinfunction "COL_4") (pintype "passive"))
    )
    (net (code "20") (name "Net-(JP2-2)") (class "Default")
      (node (ref "JP2") (pin "P$2") (pinfunction "2_P$2") (pintype "passive"))
      (node (ref "R15") (pin "2") (pinfunction "2_2") (pintype "passive"))
      (node (ref "R62") (pin "1") (pinfunction "1_1") (pintype "passive"))
    )
    (net (code "21") (name "Net-(JP3-2)") (class "Default")
      (node (ref "JP3") (pin "P$2") (pinfunction "2_P$2") (pintype "passive"))
      (node (ref "R1") (pin "2") (pinfunction "2_2") (pintype "passive"))
      (node (ref "R48") (pin "1") (pinfunction "1_1") (pintype "passive"))
    )
    (net (code "22") (name "Net-(JP4-Pad2)") (class "Default")
      (node (ref "JP4") (pin "2") (pinfunction "2_2") (pintype "passive"))
      (node (ref "R41") (pin "1") (pinfunction "1_1") (pintype "passive"))
      (node (ref "R62") (pin "2") (pinfunction "2_2") (pintype "passive"))
    )
    (net (code "23") (name "Net-(OK1-A)") (class "Default")
      (node (ref "OK1") (pin "1") (pinfunction "A_1") (pintype "passive"))
      (node (ref "R61") (pin "2") (pinfunction "2_2") (pintype "passive"))
    )
    (net (code "24") (name "Net-(OK1-EMIT)") (class "Default")
      (node (ref "OK1") (pin "3") (pinfunction "EMIT_3") (pintype "passive"))
      (node (ref "R60") (pin "2") (pinfunction "2_2") (pintype "passive"))
    )
    (net (code "25") (name "Net-(OK3-A)") (class "Default")
      (node (ref "C5") (pin "1") (pinfunction "1_1") (pintype "passive"))
      (node (ref "OK3") (pin "1") (pinfunction "A_1") (pintype "passive"))
      (node (ref "R21") (pin "1") (pinfunction "1_1") (pintype "passive"))
    )
    (net (code "26") (name "Net-(OK4-A)") (class "Default")
      (node (ref "OK4") (pin "1") (pinfunction "A_1") (pintype "passive"))
      (node (ref "R23") (pin "1") (pinfunction "1_1") (pintype "passive"))
    )
    (net (code "27") (name "Net-(OK4-COL)") (class "Default")
      (node (ref "OK4") (pin "4") (pinfunction "COL_4") (pintype "passive"))
      (node (ref "R24") (pin "1") (pinfunction "1_1") (pintype "passive"))
      (node (ref "U1") (pin "P$3") (pinfunction "G27_P$3") (pintype "bidirectional"))
    )
    (net (code "28") (name "Net-(Q1-G)") (class "Default")
      (node (ref "Q1") (pin "4") (pinfunction "G_4") (pintype "passive"))
      (node (ref "Q6") (pin "G") (pinfunction "G_G") (pintype "passive"))
      (node (ref "R57") (pin "2") (pinfunction "2_2") (pintype "passive"))
    )
    (net (code "29") (name "Net-(Q1-S-Pad1)") (class "Default")
      (node (ref "Q1") (pin "1") (pinfunction "S_1") (pintype "passive"))
      (node (ref "Q1") (pin "2") (pinfunction "S_2") (pintype "passive"))
      (node (ref "Q1") (pin "3") (pinfunction "S_3") (pintype "passive"))
      (node (ref "Q6") (pin "S") (pinfunction "S_S") (pintype "passive"))
      (node (ref "R17") (pin "2") (pinfunction "2_2") (pintype "passive"))
      (node (ref "R44") (pin "2") (pinfunction "2_2") (pintype "passive"))
      (node (ref "R50") (pin "2") (pinfunction "2_2") (pintype "passive"))
    )
    (net (code "30") (name "Net-(Q3-PadB)") (class "Default")
      (node (ref "Q3") (pin "B") (pinfunction "B_B") (pintype "passive"))
      (node (ref "R32") (pin "2") (pinfunction "2_2") (pintype "passive"))
    )
    (net (code "31") (name "Net-(Q3-PadC)") (class "Default")
      (node (ref "Q3") (pin "C") (pinfunction "C_C") (pintype "passive"))
      (node (ref "R66") (pin "1") (pinfunction "1_1") (pintype "passive"))
    )
    (net (code "32") (name "Net-(Q4-PadB)") (class "Default")
      (node (ref "Q4") (pin "B") (pinfunction "B_B") (pintype "passive"))
      (node (ref "R42") (pin "1") (pinfunction "1_1") (pintype "passive"))
      (node (ref "R43") (pin "2") (pinfunction "2_2") (pintype "passive"))
    )
    (net (code "33") (name "Net-(Q4-PadC)") (class "Default")
      (node (ref "Q4") (pin "C") (pinfunction "C_C") (pintype "passive"))
      (node (ref "R32") (pin "1") (pinfunction "1_1") (pintype "passive"))
      (node (ref "R40") (pin "1") (pinfunction "1_1") (pintype "passive"))
    )
    (net (code "34") (name "Net-(Q5-G)") (class "Default")
      (node (ref "Q5") (pin "4") (pinfunction "G_4") (pintype "passive"))
      (node (ref "R46") (pin "2") (pinfunction "2_2") (pintype "passive"))
      (node (ref "U$3") (pin "3") (pinfunction "C_3") (pintype "passive"))
    )
    (net (code "35") (name "Net-(Q8-G)") (class "Default")
      (node (ref "Q8") (pin "4") (pinfunction "G_4") (pintype "passive"))
      (node (ref "R10") (pin "2") (pinfunction "2_2") (pintype "passive"))
      (node (ref "U$2") (pin "3") (pinfunction "C_3") (pintype "passive"))
    )
    (net (code "36") (name "Net-(Q12-G)") (class "Default")
      (node (ref "C12") (pin "1") (pinfunction "1_1") (pintype "passive"))
      (node (ref "Q12") (pin "4") (pinfunction "G_4") (pintype "passive"))
      (node (ref "Q7") (pin "G") (pinfunction "G_G") (pintype "passive"))
      (node (ref "R30") (pin "2") (pinfunction "2_2") (pintype "passive"))
      (node (ref "R31") (pin "2") (pinfunction "2_2") (pintype "passive"))
    )
    (net (code "37") (name "Net-(Q13-G)") (class "Default")
      (node (ref "Q13") (pin "4") (pinfunction "G_4") (pintype "passive"))
      (node (ref "Q2") (pin "4") (pinfunction "G_4") (pintype "passive"))
      (node (ref "R39") (pin "1") (pinfunction "1_1") (pintype "passive"))
      (node (ref "R66") (pin "2") (pinfunction "2_2") (pintype "passive"))
      (node (ref "R67") (pin "2") (pinfunction "2_2") (pintype "passive"))
    )
    (net (code "38") (name "Net-(Q13-S-Pad1)") (class "Default")
      (node (ref "Q13") (pin "1") (pinfunction "S_1") (pintype "passive"))
      (node (ref "Q13") (pin "2") (pinfunction "S_2") (pintype "passive"))
      (node (ref "Q13") (pin "3") (pinfunction "S_3") (pintype "passive"))
      (node (ref "Q2") (pin "1") (pinfunction "S_1") (pintype "passive"))
      (node (ref "Q2") (pin "2") (pinfunction "S_2") (pintype "passive"))
      (node (ref "Q2") (pin "3") (pinfunction "S_3") (pintype "passive"))
      (node (ref "R39") (pin "2") (pinfunction "2_2") (pintype "passive"))
    )
    (net (code "39") (name "Net-(R14-Pad2)") (class "Default")
      (node (ref "R14") (pin "2") (pinfunction "2_2") (pintype "passive"))
      (node (ref "R2") (pin "2") (pinfunction "2_2") (pintype "passive"))
      (node (ref "R51") (pin "1") (pinfunction "1_1") (pintype "passive"))
    )
    (net (code "40") (name "Net-(R20-Pad2)") (class "Default")
      (node (ref "R20") (pin "2") (pinfunction "2_2") (pintype "passive"))
      (node (ref "R34") (pin "1") (pinfunction "1_1") (pintype "passive"))
    )
    (net (code "41") (name "Net-(R35-Pad1)") (class "Default")
      (node (ref "R35") (pin "1") (pinfunction "1_1") (pintype "passive"))
      (node (ref "R5") (pin "2") (pinfunction "2_2") (pintype "passive"))
    )
    (net (code "42") (name "Net-(R49-Pad1)") (class "Default")
      (node (ref "R49") (pin "1") (pinfunction "1_1") (pintype "passive"))
      (node (ref "R50") (pin "1") (pinfunction "1_1") (pintype "passive"))
    )
    (net (code "43") (name "Net-(S1-P)") (class "Default")
      (node (ref "C8") (pin "1") (pinfunction "1_1") (pintype "passive"))
      (node (ref "D6") (pin "C") (pinfunction "C_C") (pintype "passive"))
      (node (ref "R28") (pin "1") (pinfunction "1_1") (pintype "passive"))
      (node (ref "S1") (pin "3") (pinfunction "P_3") (pintype "passive"))
      (node (ref "U1") (pin "P$10") (pinfunction "G37_P$10") (pintype "bidirectional"))
    )
    (net (code "44") (name "Net-(S2-P)") (class "Default")
      (node (ref "C9") (pin "1") (pinfunction "1_1") (pintype "passive"))
      (node (ref "D7") (pin "C") (pinfunction "C_C") (pintype "passive"))
      (node (ref "R27") (pin "1") (pinfunction "1_1") (pintype "passive"))
      (node (ref "S2") (pin "3") (pinfunction "P_3") (pintype "passive"))
      (node (ref "U1") (pin "P$15") (pinfunction "G21_P$15") (pintype "bidirectional"))
    )
    (net (code "45") (name "Net-(S3-P)") (class "Default")
      (node (ref "C10") (pin "1") (pinfunction "1_1") (pintype "passive"))
      (node (ref "D5") (pin "C") (pinfunction "C_C") (pintype "passive"))
      (node (ref "R26") (pin "1") (pinfunction "1_1") (pintype "passive"))
      (node (ref "S3") (pin "3") (pinfunction "P_3") (pintype "passive"))
      (node (ref "U1") (pin "P$9") (pinfunction "G38_P$9") (pintype "bidirectional"))
    )
    (net (code "46") (name "Net-(S4-P)") (class "Default")
      (node (ref "C11") (pin "1") (pinfunction "1_1") (pintype "passive"))
      (node (ref "D4") (pin "C") (pinfunction "C_C") (pintype "passive"))
      (node (ref "R25") (pin "1") (pinfunction "1_1") (pintype "passive"))
      (node (ref "S4") (pin "3") (pinfunction "P_3") (pintype "passive"))
      (node (ref "U1") (pin "P$5") (pinfunction "G25_P$5") (pintype "bidirectional"))
    )
    (net (code "47") (name "Net-(T1-B)") (class "Default")
      (node (ref "R52") (pin "1") (pinfunction "1_1") (pintype "passive"))
      (node (ref "T1") (pin "1") (pinfunction "B_1") (pintype "passive"))
    )
    (net (code "48") (name "Net-(T2-B)") (class "Default")
      (node (ref "R55") (pin "1") (pinfunction "1_1") (pintype "passive"))
      (node (ref "T2") (pin "1") (pinfunction "B_1") (pintype "passive"))
    )
    (net (code "49") (name "Net-(T2-C)") (class "Default")
      (node (ref "Q11") (pin "B") (pinfunction "B_B") (pintype "passive"))
      (node (ref "R54") (pin "1") (pinfunction "1_1") (pintype "passive"))
      (node (ref "T2") (pin "3") (pinfunction "C_3") (pintype "passive"))
    )
    (net (code "50") (name "Net-(T2-E)") (class "Default")
      (node (ref "R45") (pin "2") (pinfunction "2_2") (pintype "passive"))
      (node (ref "R53") (pin "1") (pinfunction "1_1") (pintype "passive"))
      (node (ref "T2") (pin "2") (pinfunction "E_2") (pintype "passive"))
    )
    (net (code "51") (name "Net-(T3-B)") (class "Default")
      (node (ref "Q11") (pin "C") (pinfunction "C_C") (pintype "passive"))
      (node (ref "R53") (pin "2") (pinfunction "2_2") (pintype "passive"))
      (node (ref "T3") (pin "1") (pinfunction "B_1") (pintype "passive"))
    )
    (net (code "52") (name "Net-(T3-E)") (class "Default")
      (node (ref "T3") (pin "2") (pinfunction "E_2") (pintype "passive"))
      (node (ref "T4") (pin "1") (pinfunction "B_1") (pintype "passive"))
    )
    (net (code "53") (name "Net-(T4-E)") (class "Default")
      (node (ref "R56") (pin "1") (pinfunction "1_1") (pintype "passive"))
      (node (ref "R57") (pin "1") (pinfunction "1_1") (pintype "passive"))
      (node (ref "T4") (pin "2") (pinfunction "E_2") (pintype "passive"))
    )
    (net (code "54") (name "Net-(T5-B)") (class "Default")
      (node (ref "R33") (pin "1") (pinfunction "1_1") (pintype "passive"))
      (node (ref "R60") (pin "1") (pinfunction "1_1") (pintype "passive"))
      (node (ref "T5") (pin "1") (pinfunction "B_1") (pintype "passive"))
    )
    (net (code "55") (name "Net-(T5-C)") (class "Default")
      (node (ref "D1") (pin "A") (pinfunction "A_A") (pintype "passive"))
      (node (ref "T5") (pin "3") (pinfunction "C_3") (pintype "passive"))
      (node (ref "U$1") (pin "COIL0") (pinfunction "COIL0_COIL0") (pintype "bidirectional"))
    )
    (net (code "56") (name "Net-(T6-B)") (class "Default")
      (node (ref "R65") (pin "2") (pinfunction "2_2") (pintype "passive"))
      (node (ref "T6") (pin "1") (pinfunction "B_1") (pintype "passive"))
    )
    (net (code "57") (name "Net-(T6-C)") (class "Default")
      (node (ref "R30") (pin "1") (pinfunction "1_1") (pintype "passive"))
      (node (ref "R64") (pin "1") (pinfunction "1_1") (pintype "passive"))
      (node (ref "T6") (pin "3") (pinfunction "C_3") (pintype "passive"))
    )
    (net (code "58") (name "Net-(U$2-B)") (class "Default")
      (node (ref "R11") (pin "2") (pinfunction "2_2") (pintype "passive"))
      (node (ref "U$2") (pin "5") (pinfunction "B_5") (pintype "passive"))
    )
    (net (code "59") (name "Net-(U$2-B1)") (class "Default")
      (node (ref "R11") (pin "1") (pinfunction "1_1") (pintype "passive"))
      (node (ref "R9") (pin "2") (pinfunction "2_2") (pintype "passive"))
      (node (ref "U$2") (pin "2") (pinfunction "B1_2") (pintype "passive"))
      (node (ref "U$2") (pin "6") (pinfunction "C1_6") (pintype "passive"))
    )
    (net (code "60") (name "Net-(U$3-B)") (class "Default")
      (node (ref "R47") (pin "2") (pinfunction "2_2") (pintype "passive"))
      (node (ref "U$3") (pin "5") (pinfunction "B_5") (pintype "passive"))
    )
    (net (code "61") (name "Net-(U$3-B1)") (class "Default")
      (node (ref "R12") (pin "2") (pinfunction "2_2") (pintype "passive"))
      (node (ref "R47") (pin "1") (pinfunction "1_1") (pintype "passive"))
      (node (ref "U$3") (pin "2") (pinfunction "B1_2") (pintype "passive"))
      (node (ref "U$3") (pin "6") (pinfunction "C1_6") (pintype "passive"))
    )
    (net (code "62") (name "Net-(U$3-E)") (class "Default")
      (node (ref "Q5") (pin "1") (pinfunction "S_1") (pintype "passive"))
      (node (ref "Q5") (pin "2") (pinfunction "S_2") (pintype "passive"))
      (node (ref "Q5") (pin "3") (pinfunction "S_3") (pintype "passive"))
      (node (ref "U$1") (pin "SWOPEN") (pinfunction "SWOPEN_SWOPEN") (pintype "bidirectional"))
      (node (ref "U$3") (pin "4") (pinfunction "E_4") (pintype "passive"))
    )
    (net (code "63") (name "Net-(U$3-E1)") (class "Default")
      (node (ref "Q5") (pin "5") (pinfunction "D_5") (pintype "passive"))
      (node (ref "Q5") (pin "6") (pinfunction "D_6") (pintype "passive"))
      (node (ref "Q5") (pin "7") (pinfunction "D_7") (pintype "passive"))
      (node (ref "Q5") (pin "8") (pinfunction "D_8") (pintype "passive"))
      (node (ref "R3") (pin "2") (pinfunction "2_2") (pintype "passive"))
      (node (ref "U$3") (pin "1") (pinfunction "E1_1") (pintype "passive"))
      (node (ref "U3") (pin "4") (pinfunction "VIN-_4") (pintype "power_in"))
    )
    (net (code "64") (name "Net-(U$5-A)") (class "Default")
      (node (ref "R4") (pin "2") (pinfunction "2_2") (pintype "passive"))
      (node (ref "U$5") (pin "P$1") (pinfunction "A_P$1") (pintype "passive"))
    )
    (net (code "65") (name "Net-(U$5-S)") (class "Default")
      (node (ref "R8") (pin "2") (pinfunction "2_2") (pintype "passive"))
      (node (ref "U$5") (pin "P$2") (pinfunction "S_P$2") (pintype "passive"))
    )
    (net (code "66") (name "Net-(U1-G12)") (class "Default")
      (node (ref "C17") (pin "1") (pinfunction "1_1") (pintype "passive"))
      (node (ref "JP4") (pin "1") (pinfunction "1_1") (pintype "passive"))
      (node (ref "U1") (pin "P$21") (pinfunction "G12_P$21") (pintype "bidirectional"))
    )
    (net (code "67") (name "Net-(U1-G13)") (class "Default")
      (node (ref "C18") (pin "1") (pinfunction "1_1") (pintype "passive"))
      (node (ref "R48") (pin "2") (pinfunction "2_2") (pintype "passive"))
      (node (ref "R63") (pin "1") (pinfunction "1_1") (pintype "passive"))
      (node (ref "U1") (pin "P$20") (pinfunction "G13_P$20") (pintype "bidirectional"))
    )
    (net (code "68") (name "Net-(U1-G15)") (class "Default")
      (node (ref "R61") (pin "1") (pinfunction "1_1") (pintype "passive"))
      (node (ref "U1") (pin "P$19") (pinfunction "G15_P$19") (pintype "bidirectional"))
    )
    (net (code "69") (name "Net-(U1-G17)") (class "Default")
      (node (ref "R21") (pin "2") (pinfunction "2_2") (pintype "passive"))
      (node (ref "U1") (pin "P$17") (pinfunction "G17_P$17") (pintype "bidirectional"))
    )
    (net (code "70") (name "Net-(U1-G22)") (class "Default")
      (node (ref "R65") (pin "1") (pinfunction "1_1") (pintype "passive"))
      (node (ref "U1") (pin "P$16") (pinfunction "G22_P$16") (pintype "bidirectional"))
    )
    (net (code "71") (name "Net-(U1-G26)") (class "Default")
      (node (ref "R58") (pin "2") (pinfunction "2_2") (pintype "passive"))
      (node (ref "R7") (pin "2") (pinfunction "2_2") (pintype "passive"))
      (node (ref "U1") (pin "P$4") (pinfunction "G26_P$4") (pintype "bidirectional"))
    )
    (net (code "72") (name "Net-(U1-G32)") (class "Default")
      (node (ref "C2") (pin "1") (pinfunction "1_1") (pintype "passive"))
      (node (ref "R20") (pin "1") (pinfunction "1_1") (pintype "passive"))
      (node (ref "R38") (pin "2") (pinfunction "2_2") (pintype "passive"))
      (node (ref "U1") (pin "P$7") (pinfunction "G32_P$7") (pintype "bidirectional"))
      (node (ref "U4") (pin "1") (pinfunction "OUT_1") (pintype "output"))
    )
    (net (code "73") (name "Net-(U1-G33)") (class "Default")
      (node (ref "C1") (pin "1") (pinfunction "1_1") (pintype "passive"))
      (node (ref "R36") (pin "1") (pinfunction "1_1") (pintype "passive"))
      (node (ref "R37") (pin "2") (pinfunction "2_2") (pintype "passive"))
      (node (ref "U1") (pin "P$6") (pinfunction "G33_P$6") (pintype "bidirectional"))
    )
    (net (code "74") (name "Net-(U1-G36)") (class "Default")
      (node (ref "C3") (pin "1") (pinfunction "1_1") (pintype "passive"))
      (node (ref "R19") (pin "2") (pinfunction "2_2") (pintype "passive"))
      (node (ref "R5") (pin "1") (pinfunction "1_1") (pintype "passive"))
      (node (ref "U1") (pin "P$11") (pinfunction "G36_P$11") (pintype "bidirectional"))
      (node (ref "U3") (pin "1") (pinfunction "OUT_1") (pintype "output"))
    )
    (net (code "75") (name "Net-(U1-G39)") (class "Default")
      (node (ref "C4") (pin "1") (pinfunction "1_1") (pintype "passive"))
      (node (ref "R17") (pin "1") (pinfunction "1_1") (pintype "passive"))
      (node (ref "R18") (pin "2") (pinfunction "2_2") (pintype "passive"))
      (node (ref "U1") (pin "P$8") (pinfunction "G39_P$8") (pintype "bidirectional"))
    )
    (net (code "76") (name "Net-(U3-VIN+)") (class "Default")
      (node (ref "Q1") (pin "5") (pinfunction "D_5") (pintype "passive"))
      (node (ref "Q1") (pin "6") (pinfunction "D_6") (pintype "passive"))
      (node (ref "Q1") (pin "7") (pinfunction "D_7") (pintype "passive"))
      (node (ref "Q1") (pin "8") (pinfunction "D_8") (pintype "passive"))
      (node (ref "Q6") (pin "D") (pinfunction "D_D") (pintype "passive"))
      (node (ref "R3") (pin "1") (pinfunction "1_1") (pintype "passive"))
      (node (ref "U3") (pin "3") (pinfunction "VIN+_3") (pintype "input"))
    )
    (net (code "77") (name "Net-(U4-VIN-)") (class "Default")
      (node (ref "R29") (pin "1") (pinfunction "1_1") (pintype "passive"))
      (node (ref "U4") (pin "4") (pinfunction "VIN-_4") (pintype "power_in"))
      (node (ref "X3") (pin "P$2") (pinfunction "2_P$2") (pintype "passive"))
      (node (ref "X3") (pin "P$4") (pinfunction "4_P$4") (pintype "passive"))
      (node (ref "X3") (pin "P$6") (pinfunction "6_P$6") (pintype "passive"))
      (node (ref "X3") (pin "P$8") (pinfunction "8_P$8") (pintype "passive"))
    )
    (net (code "78") (name "Net-(X3-1)") (class "Default")
      (node (ref "Q12") (pin "5") (pinfunction "D_5") (pintype "passive"))
      (node (ref "Q12") (pin "6") (pinfunction "D_6") (pintype "passive"))
      (node (ref "Q12") (pin "7") (pinfunction "D_7") (pintype "passive"))
      (node (ref "Q12") (pin "8") (pinfunction "D_8") (pintype "passive"))
      (node (ref "Q7") (pin "D") (pinfunction "D_D") (pintype "passive"))
      (node (ref "X3") (pin "P$1") (pinfunction "1_P$1") (pintype "passive"))
      (node (ref "X3") (pin "P$3") (pinfunction "3_P$3") (pintype "passive"))
      (node (ref "X3") (pin "P$5") (pinfunction "5_P$5") (pintype "passive"))
      (node (ref "X3") (pin "P$7") (pinfunction "7_P$7") (pintype "passive"))
    )
    (net (code "79") (name "VCC") (class "Default")
      (node (ref "C14") (pin "1") (pinfunction "1_1") (pintype "passive"))
      (node (ref "C16") (pin "+") (pinfunction "+_+") (pintype "passive"))
      (node (ref "C19") (pin "1") (pinfunction "1_1") (pintype "passive"))
      (node (ref "D2") (pin "C") (pinfunction "C_C") (pintype "passive"))
      (node (ref "IC1") (pin "4") (pinfunction "V+_4") (pintype "power_in"))
      (node (ref "IC2") (pin "IN") (pinfunction "IN_IN") (pintype "input"))
      (node (ref "OK1") (pin "4") (pinfunction "COL_4") (pintype "passive"))
      (node (ref "Q2") (pin "5") (pinfunction "D_5") (pintype "passive"))
      (node (ref "Q2") (pin "6") (pinfunction "D_6") (pintype "passive"))
      (node (ref "Q2") (pin "7") (pinfunction "D_7") (pintype "passive"))
      (node (ref "Q2") (pin "8") (pinfunction "D_8") (pintype "passive"))
      (node (ref "Q8") (pin "1") (pinfunction "S_1") (pintype "passive"))
      (node (ref "Q8") (pin "2") (pinfunction "S_2") (pintype "passive"))
      (node (ref "Q8") (pin "3") (pinfunction "S_3") (pintype "passive"))
      (node (ref "R29") (pin "2") (pinfunction "2_2") (pintype "passive"))
      (node (ref "R4") (pin "1") (pinfunction "1_1") (pintype "passive"))
      (node (ref "R59") (pin "1") (pinfunction "1_1") (pintype "passive"))
      (node (ref "R64") (pin "2") (pinfunction "2_2") (pintype "passive"))
      (node (ref "U$2") (pin "4") (pinfunction "E_4") (pintype "passive"))
      (node (ref "U4") (pin "3") (pinfunction "VIN+_3") (pintype "input"))
    )
    (net (code "80") (name "unconnected-(JP2-1-PadP$1)") (class "Default")
      (node (ref "JP2") (pin "P$1") (pinfunction "1_P$1") (pintype "passive"))
    )
    (net (code "81") (name "unconnected-(JP3-1-PadP$1)") (class "Default")
      (node (ref "JP3") (pin "P$1") (pinfunction "1_P$1") (pintype "passive"))
    )
    (net (code "82") (name "unconnected-(S1-P1-Pad4)") (class "Default")
      (node (ref "S1") (pin "4") (pinfunction "P1_4") (pintype "passive"))
    )
    (net (code "83") (name "unconnected-(S1-S1-Pad2)") (class "Default")
      (node (ref "S1") (pin "2") (pinfunction "S1_2") (pintype "passive"))
    )
    (net (code "84") (name "unconnected-(S2-P1-Pad4)") (class "Default")
      (node (ref "S2") (pin "4") (pinfunction "P1_4") (pintype "passive"))
    )
    (net (code "85") (name "unconnected-(S2-S1-Pad2)") (class "Default")
      (node (ref "S2") (pin "2") (pinfunction "S1_2") (pintype "passive"))
    )
    (net (code "86") (name "unconnected-(S3-P1-Pad4)") (class "Default")
      (node (ref "S3") (pin "4") (pinfunction "P1_4") (pintype "passive"))
    )
    (net (code "87") (name "unconnected-(S3-S1-Pad2)") (class "Default")
      (node (ref "S3") (pin "2") (pinfunction "S1_2") (pintype "passive"))
    )
    (net (code "88") (name "unconnected-(S4-P1-Pad4)") (class "Default")
      (node (ref "S4") (pin "4") (pinfunction "P1_4") (pintype "passive"))
    )
    (net (code "89") (name "unconnected-(S4-S1-Pad2)") (class "Default")
      (node (ref "S4") (pin "2") (pinfunction "S1_2") (pintype "passive"))
    )
    (net (code "90") (name "unconnected-(U$1-SWCLOSE-PadSWCLOSED)") (class "Default")
      (node (ref "U$1") (pin "SWCLOSED") (pinfunction "SWCLOSE_SWCLOSED") (pintype "bidirectional"))
    )
    (net (code "91") (name "unconnected-(U1-G2-PadP$18)") (class "Default")
      (node (ref "U1") (pin "P$18") (pinfunction "G2_P$18") (pintype "bidirectional"))
    )
  )
)
